# temp_sensor.net
KiCad netlist of a schematic drawn in EAGLE
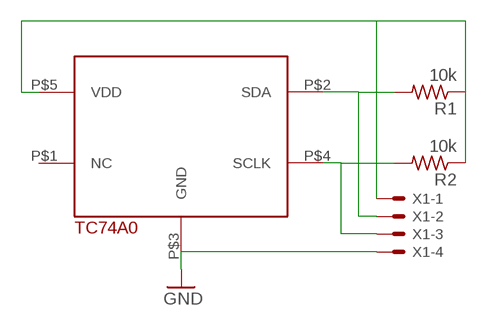
[diagram p0: schematic, sheet 1]

(export (version "E")
  (design (tool "Eeschema 10.0.6"))
  (components
    (comp (ref "R1")
      (value "10k")
      (footprint "eagle-import:R0805")
      (libsource (lib "eagle-import") (part "R-US_R0805"))
    )
    (comp (ref "R2")
      (value "10k")
      (footprint "eagle-import:R0805")
      (libsource (lib "eagle-import") (part "R-US_R0805"))
    )
    (comp (ref "U$1")
      (value "TC74A0")
      (footprint "eagle-import:TC74A0")
      (libsource (lib "eagle-import") (part "TC74A0"))
    )
    (comp (ref "X1")
      (value "KK-156-4")
      (footprint "eagle-import:KK-156-4")
      (libsource (lib "eagle-import") (part "KK-156-4"))
    )
  )
  (nets
    (net (code "1") (name "GND") (class "Default")
      (node (ref "U$1") (pin "P$3") (pinfunction "GND_P$3") (pintype "bidirectional"))
      (node (ref "X1") (pin "4") (pinfunction "S_4") (pintype "passive"))
    )
    (net (code "2") (name "Net-(U$1-SCLK)") (class "Default")
      (node (ref "R2") (pin "2") (pinfunction "2_2") (pintype "passive"))
      (node (ref "U$1") (pin "P$4") (pinfunction "SCLK_P$4") (pintype "bidirectional"))
      (node (ref "X1") (pin "3") (pinfunction "S_3") (pintype "passive"))
    )
    (net (code "3") (name "Net-(U$1-SDA)") (class "Default")
      (node (ref "R1") (pin "2") (pinfunction "2_2") (pintype "passive"))
      (node (ref "U$1") (pin "P$2") (pinfunction "SDA_P$2") (pintype "bidirectional"))
      (node (ref "X1") (pin "2") (pinfunction "S_2") (pintype "passive"))
    )
    (net (code "4") (name "Net-(U$1-VDD)") (class "Default")
      (node (ref "R1") (pin "1") (pinfunction "1_1") (pintype "passive"))
      (node (ref "R2") (pin "1") (pinfunction "1_1") (pintype "passive"))
      (node (ref "U$1") (pin "P$5") (pinfunction "VDD_P$5") (pintype "bidirectional"))
      (node (ref "X1") (pin "1") (pinfunction "S_1") (pintype "passive"))
    )
    (net (code "5") (name "unconnected-(U$1-NC-PadP$1)") (class "Default")
      (node (ref "U$1") (pin "P$1") (pinfunction "NC_P$1") (pintype "bidirectional"))
    )
  )
)
